# Memory-QSPI_Flash-eMMC.net
KiCad netlist of a schematic drawn in Altium Designer
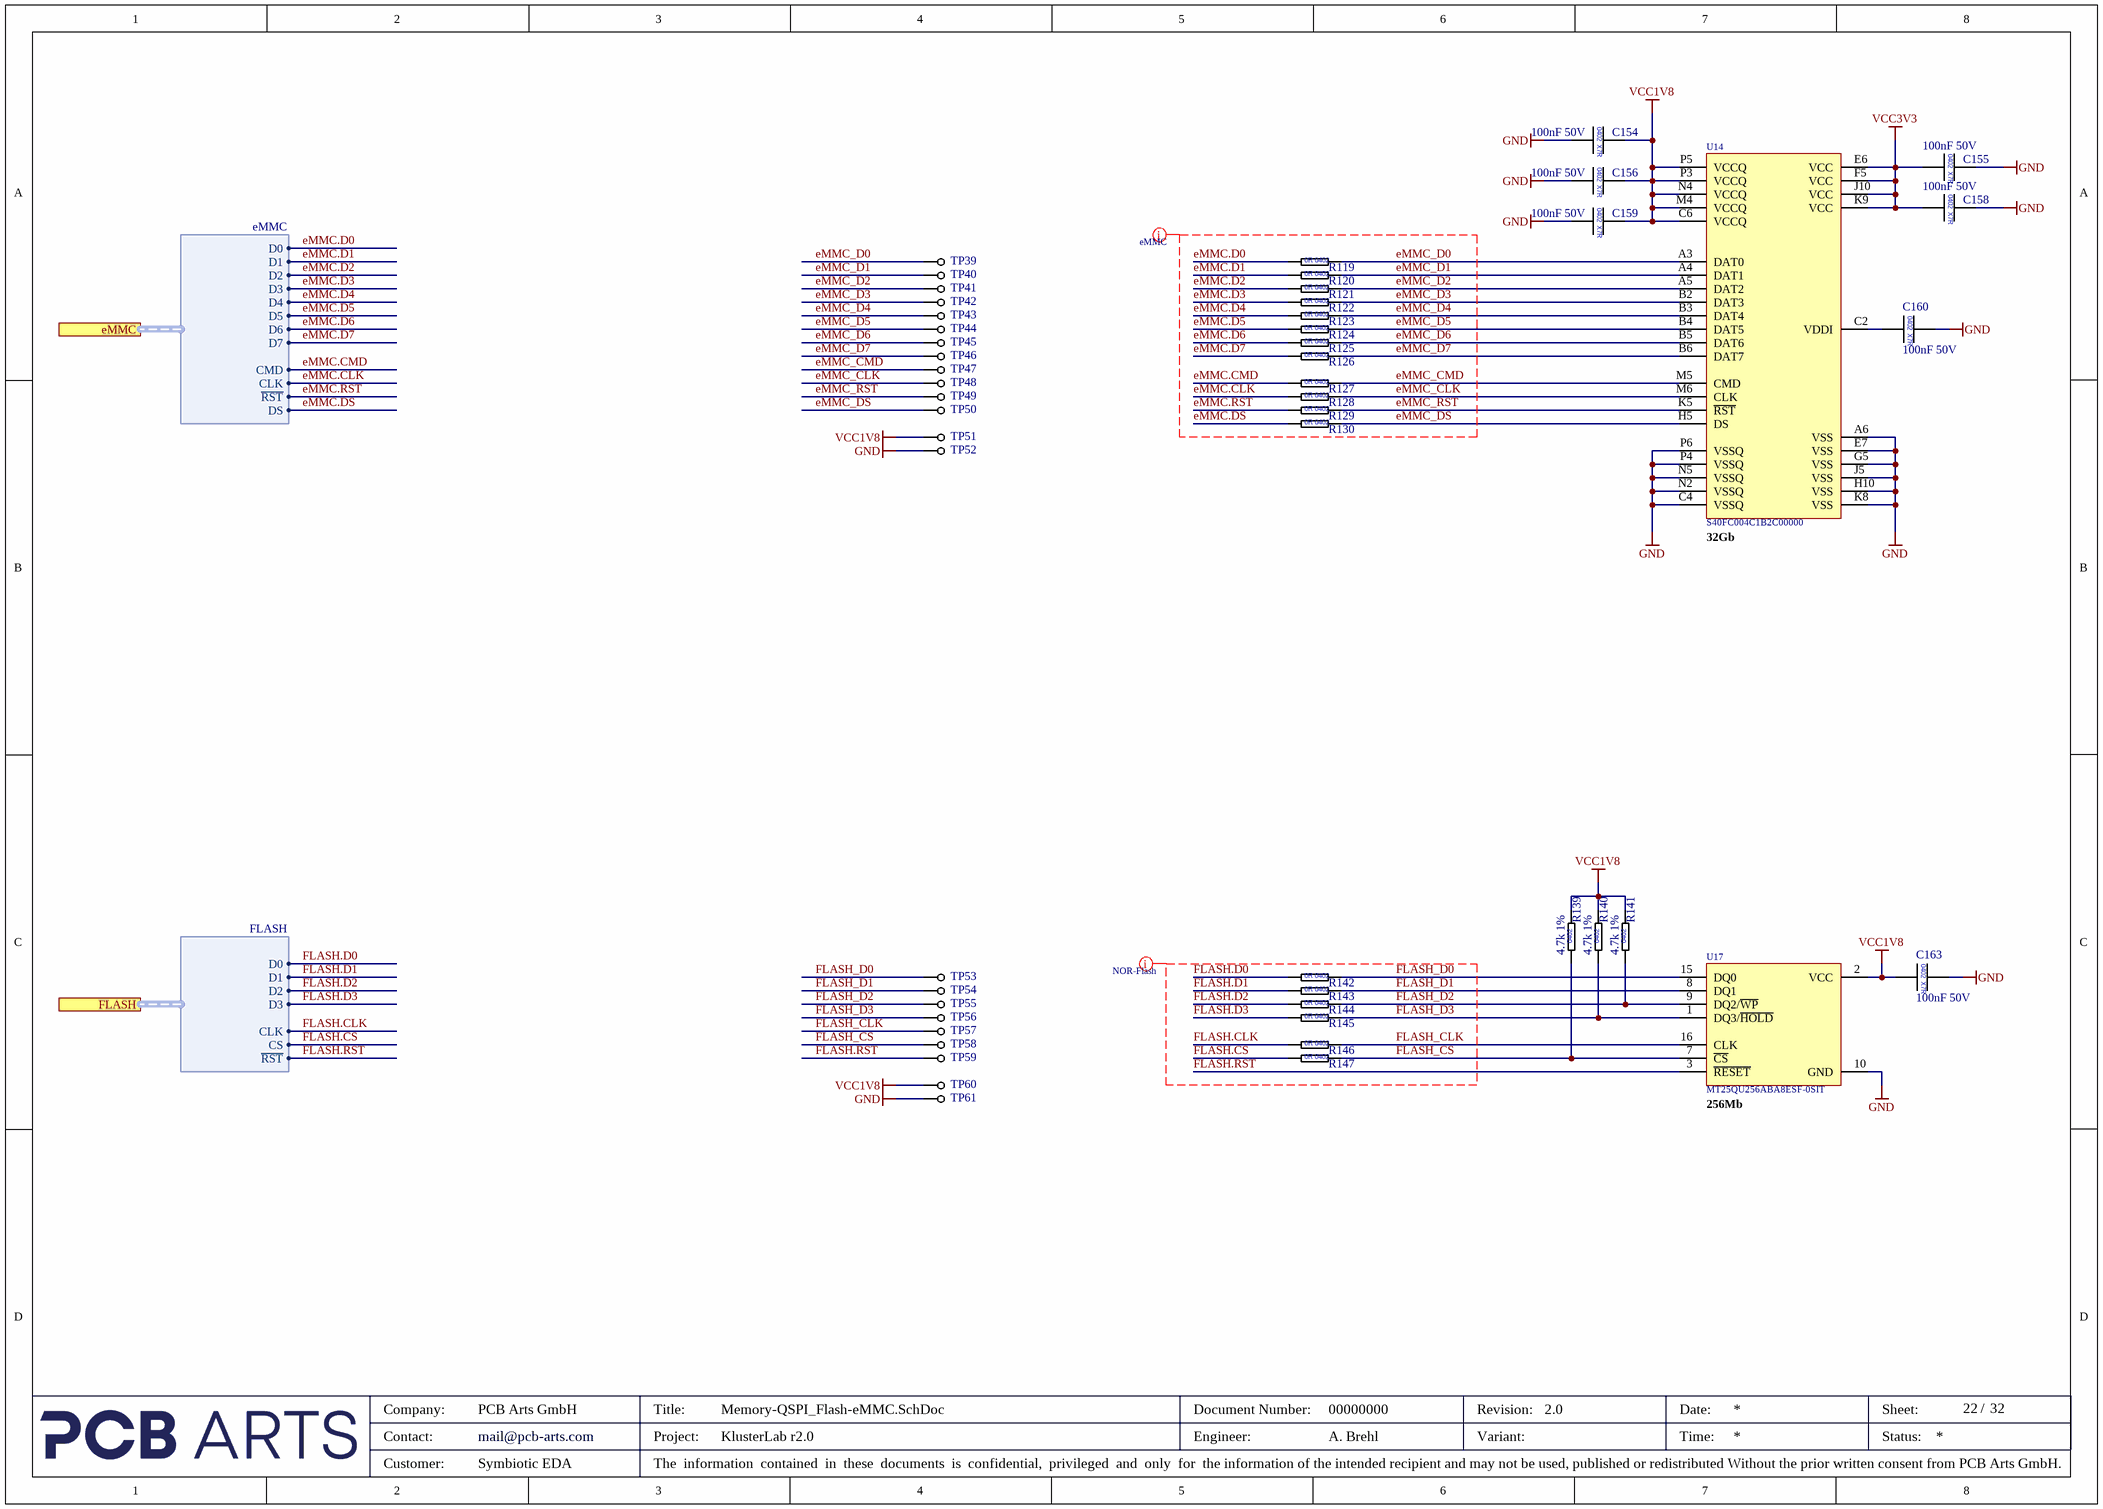
[diagram p0: Memory-QSPI_Flash-eMMC.SchDoc]

(export (version "E")
  (design (tool "Eeschema 10.0.6"))
  (components
    (comp (ref "C154")
      (value "100nF 50V")
      (footprint "Cap:CAP_0402_L")
      (description "Multilayer Ceramic Capacitors MLCC - SMD/SMT 0402 50VDC")
      (libsource (lib "Cap") (part "CAP_0402_100nF_50V"))
    )
    (comp (ref "C155")
      (value "100nF 50V")
      (footprint "Cap:CAP_0402_L")
      (description "Multilayer Ceramic Capacitors MLCC - SMD/SMT 0402 50VDC")
      (libsource (lib "Cap") (part "CAP_0402_100nF_50V"))
    )
    (comp (ref "C156")
      (value "100nF 50V")
      (footprint "Cap:CAP_0402_L")
      (description "Multilayer Ceramic Capacitors MLCC - SMD/SMT 0402 50VDC")
      (libsource (lib "Cap") (part "CAP_0402_100nF_50V"))
    )
    (comp (ref "C158")
      (value "100nF 50V")
      (footprint "Cap:CAP_0402_L")
      (description "Multilayer Ceramic Capacitors MLCC - SMD/SMT 0402 50VDC")
      (libsource (lib "Cap") (part "CAP_0402_100nF_50V"))
    )
    (comp (ref "C159")
      (value "100nF 50V")
      (footprint "Cap:CAP_0402_L")
      (description "Multilayer Ceramic Capacitors MLCC - SMD/SMT 0402 50VDC")
      (libsource (lib "Cap") (part "CAP_0402_100nF_50V"))
    )
    (comp (ref "C160")
      (value "100nF 50V")
      (footprint "Cap:CAP_0402_L")
      (description "Multilayer Ceramic Capacitors MLCC - SMD/SMT 0402 50VDC")
      (libsource (lib "Cap") (part "CAP_0402_100nF_50V"))
    )
    (comp (ref "C163")
      (value "100nF 50V")
      (footprint "Cap:CAP_0402_L")
      (description "Multilayer Ceramic Capacitors MLCC - SMD/SMT 0402 50VDC")
      (libsource (lib "Cap") (part "CAP_0402_100nF_50V"))
    )
    (comp (ref "R119")
      (value "0R Jumper")
      (footprint "Res:RES_0402_L")
      (description "Thick Film Resistors - SMD 0Ohm")
      (libsource (lib "Res") (part "RES_0402_0R Jumper"))
    )
    (comp (ref "R120")
      (value "0R Jumper")
      (footprint "Res:RES_0402_L")
      (description "Thick Film Resistors - SMD 0Ohm")
      (libsource (lib "Res") (part "RES_0402_0R Jumper"))
    )
    (comp (ref "R121")
      (value "0R Jumper")
      (footprint "Res:RES_0402_L")
      (description "Thick Film Resistors - SMD 0Ohm")
      (libsource (lib "Res") (part "RES_0402_0R Jumper"))
    )
    (comp (ref "R122")
      (value "0R Jumper")
      (footprint "Res:RES_0402_L")
      (description "Thick Film Resistors - SMD 0Ohm")
      (libsource (lib "Res") (part "RES_0402_0R Jumper"))
    )
    (comp (ref "R123")
      (value "0R Jumper")
      (footprint "Res:RES_0402_L")
      (description "Thick Film Resistors - SMD 0Ohm")
      (libsource (lib "Res") (part "RES_0402_0R Jumper"))
    )
    (comp (ref "R124")
      (value "0R Jumper")
      (footprint "Res:RES_0402_L")
      (description "Thick Film Resistors - SMD 0Ohm")
      (libsource (lib "Res") (part "RES_0402_0R Jumper"))
    )
    (comp (ref "R125")
      (value "0R Jumper")
      (footprint "Res:RES_0402_L")
      (description "Thick Film Resistors - SMD 0Ohm")
      (libsource (lib "Res") (part "RES_0402_0R Jumper"))
    )
    (comp (ref "R126")
      (value "0R Jumper")
      (footprint "Res:RES_0402_L")
      (description "Thick Film Resistors - SMD 0Ohm")
      (libsource (lib "Res") (part "RES_0402_0R Jumper"))
    )
    (comp (ref "R127")
      (value "0R Jumper")
      (footprint "Res:RES_0402_L")
      (description "Thick Film Resistors - SMD 0Ohm")
      (libsource (lib "Res") (part "RES_0402_0R Jumper"))
    )
    (comp (ref "R128")
      (value "0R Jumper")
      (footprint "Res:RES_0402_L")
      (description "Thick Film Resistors - SMD 0Ohm")
      (libsource (lib "Res") (part "RES_0402_0R Jumper"))
    )
    (comp (ref "R129")
      (value "0R Jumper")
      (footprint "Res:RES_0402_L")
      (description "Thick Film Resistors - SMD 0Ohm")
      (libsource (lib "Res") (part "RES_0402_0R Jumper"))
    )
    (comp (ref "R130")
      (value "0R Jumper")
      (footprint "Res:RES_0402_L")
      (description "Thick Film Resistors - SMD 0Ohm")
      (libsource (lib "Res") (part "RES_0402_0R Jumper"))
    )
    (comp (ref "R139")
      (value "4.7k 1%")
      (footprint "Res:RES_0402_L")
      (description "Thick Film Resistors - SMD 4.7kOhm 1%")
      (libsource (lib "Res") (part "RES_0402_4.7k_1%"))
    )
    (comp (ref "R140")
      (value "4.7k 1%")
      (footprint "Res:RES_0402_L")
      (description "Thick Film Resistors - SMD 4.7kOhm 1%")
      (libsource (lib "Res") (part "RES_0402_4.7k_1%"))
    )
    (comp (ref "R141")
      (value "4.7k 1%")
      (footprint "Res:RES_0402_L")
      (description "Thick Film Resistors - SMD 4.7kOhm 1%")
      (libsource (lib "Res") (part "RES_0402_4.7k_1%"))
    )
    (comp (ref "R142")
      (value "0R Jumper")
      (footprint "Res:RES_0402_L")
      (description "Thick Film Resistors - SMD 0Ohm")
      (libsource (lib "Res") (part "RES_0402_0R Jumper"))
    )
    (comp (ref "R143")
      (value "0R Jumper")
      (footprint "Res:RES_0402_L")
      (description "Thick Film Resistors - SMD 0Ohm")
      (libsource (lib "Res") (part "RES_0402_0R Jumper"))
    )
    (comp (ref "R144")
      (value "0R Jumper")
      (footprint "Res:RES_0402_L")
      (description "Thick Film Resistors - SMD 0Ohm")
      (libsource (lib "Res") (part "RES_0402_0R Jumper"))
    )
    (comp (ref "R145")
      (value "0R Jumper")
      (footprint "Res:RES_0402_L")
      (description "Thick Film Resistors - SMD 0Ohm")
      (libsource (lib "Res") (part "RES_0402_0R Jumper"))
    )
    (comp (ref "R146")
      (value "0R Jumper")
      (footprint "Res:RES_0402_L")
      (description "Thick Film Resistors - SMD 0Ohm")
      (libsource (lib "Res") (part "RES_0402_0R Jumper"))
    )
    (comp (ref "R147")
      (value "0R Jumper")
      (footprint "Res:RES_0402_L")
      (description "Thick Film Resistors - SMD 0Ohm")
      (libsource (lib "Res") (part "RES_0402_0R Jumper"))
    )
    (comp (ref "TP39")
      (value "Testpoint")
      (footprint "Electro_mech:Testpoint 0.8mm")
      (description "Testpoint 0.8mm")
      (libsource (lib "Electro_Mech") (part "Testpoint 0.8mm"))
    )
    (comp (ref "TP40")
      (value "Testpoint")
      (footprint "Electro_mech:Testpoint 0.8mm")
      (description "Testpoint 0.8mm")
      (libsource (lib "Electro_Mech") (part "Testpoint 0.8mm"))
    )
    (comp (ref "TP41")
      (value "Testpoint")
      (footprint "Electro_mech:Testpoint 0.8mm")
      (description "Testpoint 0.8mm")
      (libsource (lib "Electro_Mech") (part "Testpoint 0.8mm"))
    )
    (comp (ref "TP42")
      (value "Testpoint")
      (footprint "Electro_mech:Testpoint 0.8mm")
      (description "Testpoint 0.8mm")
      (libsource (lib "Electro_Mech") (part "Testpoint 0.8mm"))
    )
    (comp (ref "TP43")
      (value "Testpoint")
      (footprint "Electro_mech:Testpoint 0.8mm")
      (description "Testpoint 0.8mm")
      (libsource (lib "Electro_Mech") (part "Testpoint 0.8mm"))
    )
    (comp (ref "TP44")
      (value "Testpoint")
      (footprint "Electro_mech:Testpoint 0.8mm")
      (description "Testpoint 0.8mm")
      (libsource (lib "Electro_Mech") (part "Testpoint 0.8mm"))
    )
    (comp (ref "TP45")
      (value "Testpoint")
      (footprint "Electro_mech:Testpoint 0.8mm")
      (description "Testpoint 0.8mm")
      (libsource (lib "Electro_Mech") (part "Testpoint 0.8mm"))
    )
    (comp (ref "TP46")
      (value "Testpoint")
      (footprint "Electro_mech:Testpoint 0.8mm")
      (description "Testpoint 0.8mm")
      (libsource (lib "Electro_Mech") (part "Testpoint 0.8mm"))
    )
    (comp (ref "TP47")
      (value "Testpoint")
      (footprint "Electro_mech:Testpoint 0.8mm")
      (description "Testpoint 0.8mm")
      (libsource (lib "Electro_Mech") (part "Testpoint 0.8mm"))
    )
    (comp (ref "TP48")
      (value "Testpoint")
      (footprint "Electro_mech:Testpoint 0.8mm")
      (description "Testpoint 0.8mm")
      (libsource (lib "Electro_Mech") (part "Testpoint 0.8mm"))
    )
    (comp (ref "TP49")
      (value "Testpoint")
      (footprint "Electro_mech:Testpoint 0.8mm")
      (description "Testpoint 0.8mm")
      (libsource (lib "Electro_Mech") (part "Testpoint 0.8mm"))
    )
    (comp (ref "TP50")
      (value "Testpoint")
      (footprint "Electro_mech:Testpoint 0.8mm")
      (description "Testpoint 0.8mm")
      (libsource (lib "Electro_Mech") (part "Testpoint 0.8mm"))
    )
    (comp (ref "TP51")
      (value "Testpoint")
      (footprint "Electro_mech:Testpoint 0.8mm")
      (description "Testpoint 0.8mm")
      (libsource (lib "Electro_Mech") (part "Testpoint 0.8mm"))
    )
    (comp (ref "TP52")
      (value "Testpoint")
      (footprint "Electro_mech:Testpoint 0.8mm")
      (description "Testpoint 0.8mm")
      (libsource (lib "Electro_Mech") (part "Testpoint 0.8mm"))
    )
    (comp (ref "TP53")
      (value "Testpoint")
      (footprint "Electro_mech:Testpoint 0.8mm")
      (description "Testpoint 0.8mm")
      (libsource (lib "Electro_Mech") (part "Testpoint 0.8mm"))
    )
    (comp (ref "TP54")
      (value "Testpoint")
      (footprint "Electro_mech:Testpoint 0.8mm")
      (description "Testpoint 0.8mm")
      (libsource (lib "Electro_Mech") (part "Testpoint 0.8mm"))
    )
    (comp (ref "TP55")
      (value "Testpoint")
      (footprint "Electro_mech:Testpoint 0.8mm")
      (description "Testpoint 0.8mm")
      (libsource (lib "Electro_Mech") (part "Testpoint 0.8mm"))
    )
    (comp (ref "TP56")
      (value "Testpoint")
      (footprint "Electro_mech:Testpoint 0.8mm")
      (description "Testpoint 0.8mm")
      (libsource (lib "Electro_Mech") (part "Testpoint 0.8mm"))
    )
    (comp (ref "TP57")
      (value "Testpoint")
      (footprint "Electro_mech:Testpoint 0.8mm")
      (description "Testpoint 0.8mm")
      (libsource (lib "Electro_Mech") (part "Testpoint 0.8mm"))
    )
    (comp (ref "TP58")
      (value "Testpoint")
      (footprint "Electro_mech:Testpoint 0.8mm")
      (description "Testpoint 0.8mm")
      (libsource (lib "Electro_Mech") (part "Testpoint 0.8mm"))
    )
    (comp (ref "TP59")
      (value "Testpoint")
      (footprint "Electro_mech:Testpoint 0.8mm")
      (description "Testpoint 0.8mm")
      (libsource (lib "Electro_Mech") (part "Testpoint 0.8mm"))
    )
    (comp (ref "TP60")
      (value "Testpoint")
      (footprint "Electro_mech:Testpoint 0.8mm")
      (description "Testpoint 0.8mm")
      (libsource (lib "Electro_Mech") (part "Testpoint 0.8mm"))
    )
    (comp (ref "TP61")
      (value "Testpoint")
      (footprint "Electro_mech:Testpoint 0.8mm")
      (description "Testpoint 0.8mm")
      (libsource (lib "Electro_Mech") (part "Testpoint 0.8mm"))
    )
    (comp (ref "U14")
      (value "S40FC004C1B2C00000")
      (footprint "Digital:BGA50P900X750X080-153N")
      (description "eMMC 4GB e.MMC5.1 BGA 9.0 x 7.5 x 0.8 mm")
      (libsource (lib "Digital") (part "S40FC004C1B2C00000_eMMC 4GB e.MMC5.1 BGA 9.0 x 7.5 x 0.8 mm"))
    )
    (comp (ref "U17")
      (value "MT25QU256ABA8ESF-0SIT")
      (footprint "Digital:SOIC16_Widebody")
      (description "NOR-Flash SPI 256Mbit NOR-Flash /1.8V")
      (libsource (lib "Digital") (part "MT25QU256ABA8ESF-0SIT_NOR-Flash SPI 256Mbit NOR-Flash /1.8V"))
    )
  )
  (nets
    (net (code "3") (name "/FLASH.CLK") (class "Default")
      (node (ref "R146") (pin "1") (pinfunction "1_1") (pintype "passive"))
    )
    (net (code "4") (name "/FLASH.D0") (class "Default")
      (node (ref "R142") (pin "1") (pinfunction "1_1") (pintype "passive"))
    )
    (net (code "5") (name "/FLASH.D1") (class "Default")
      (node (ref "R143") (pin "1") (pinfunction "1_1") (pintype "passive"))
    )
    (net (code "6") (name "/FLASH.D2") (class "Default")
      (node (ref "R144") (pin "1") (pinfunction "1_1") (pintype "passive"))
    )
    (net (code "7") (name "/FLASH.D3") (class "Default")
      (node (ref "R145") (pin "1") (pinfunction "1_1") (pintype "passive"))
    )
    (net (code "8") (name "/FLASH.~{CS}") (class "Default")
      (node (ref "R147") (pin "1") (pinfunction "1_1") (pintype "passive"))
    )
    (net (code "9") (name "/FLASH.~{RST}") (class "Default")
      (node (ref "TP59") (pin "1") (pinfunction "GND_1") (pintype "passive"))
      (node (ref "U17") (pin "3") (pinfunction "~{RESET}_3") (pintype "passive"))
    )
    (net (code "10") (name "/FLASH_CLK") (class "Default")
      (node (ref "R146") (pin "2") (pinfunction "2_2") (pintype "passive"))
      (node (ref "TP57") (pin "1") (pinfunction "GND_1") (pintype "passive"))
      (node (ref "U17") (pin "16") (pinfunction "CLK_16") (pintype "passive"))
    )
    (net (code "11") (name "/FLASH_D0") (class "Default")
      (node (ref "R142") (pin "2") (pinfunction "2_2") (pintype "passive"))
      (node (ref "TP53") (pin "1") (pinfunction "GND_1") (pintype "passive"))
      (node (ref "U17") (pin "15") (pinfunction "DQ0_15") (pintype "passive"))
    )
    (net (code "12") (name "/FLASH_D1") (class "Default")
      (node (ref "R143") (pin "2") (pinfunction "2_2") (pintype "passive"))
      (node (ref "TP54") (pin "1") (pinfunction "GND_1") (pintype "passive"))
      (node (ref "U17") (pin "8") (pinfunction "DQ1_8") (pintype "passive"))
    )
    (net (code "13") (name "/FLASH_D2") (class "Default")
      (node (ref "R141") (pin "1") (pinfunction "1_1") (pintype "passive"))
      (node (ref "R144") (pin "2") (pinfunction "2_2") (pintype "passive"))
      (node (ref "TP55") (pin "1") (pinfunction "GND_1") (pintype "passive"))
      (node (ref "U17") (pin "9") (pinfunction "DQ2/~{WP}_9") (pintype "passive"))
    )
    (net (code "14") (name "/FLASH_D3") (class "Default")
      (node (ref "R140") (pin "1") (pinfunction "1_1") (pintype "passive"))
      (node (ref "R145") (pin "2") (pinfunction "2_2") (pintype "passive"))
      (node (ref "TP56") (pin "1") (pinfunction "GND_1") (pintype "passive"))
      (node (ref "U17") (pin "1") (pinfunction "DQ3/~{HOLD}_1") (pintype "passive"))
    )
    (net (code "15") (name "/FLASH_~{CS}") (class "Default")
      (node (ref "R139") (pin "1") (pinfunction "1_1") (pintype "passive"))
      (node (ref "R147") (pin "2") (pinfunction "2_2") (pintype "passive"))
      (node (ref "TP58") (pin "1") (pinfunction "GND_1") (pintype "passive"))
      (node (ref "U17") (pin "7") (pinfunction "~{CS}_7") (pintype "passive"))
    )
    (net (code "16") (name "/eMMC.CLK") (class "Default")
      (node (ref "R128") (pin "1") (pinfunction "1_1") (pintype "passive"))
    )
    (net (code "17") (name "/eMMC.CMD") (class "Default")
      (node (ref "R127") (pin "1") (pinfunction "1_1") (pintype "passive"))
    )
    (net (code "18") (name "/eMMC.D0") (class "Default")
      (node (ref "R119") (pin "1") (pinfunction "1_1") (pintype "passive"))
    )
    (net (code "19") (name "/eMMC.D1") (class "Default")
      (node (ref "R120") (pin "1") (pinfunction "1_1") (pintype "passive"))
    )
    (net (code "20") (name "/eMMC.D2") (class "Default")
      (node (ref "R121") (pin "1") (pinfunction "1_1") (pintype "passive"))
    )
    (net (code "21") (name "/eMMC.D3") (class "Default")
      (node (ref "R122") (pin "1") (pinfunction "1_1") (pintype "passive"))
    )
    (net (code "22") (name "/eMMC.D4") (class "Default")
      (node (ref "R123") (pin "1") (pinfunction "1_1") (pintype "passive"))
    )
    (net (code "23") (name "/eMMC.D5") (class "Default")
      (node (ref "R124") (pin "1") (pinfunction "1_1") (pintype "passive"))
    )
    (net (code "24") (name "/eMMC.D6") (class "Default")
      (node (ref "R125") (pin "1") (pinfunction "1_1") (pintype "passive"))
    )
    (net (code "25") (name "/eMMC.D7") (class "Default")
      (node (ref "R126") (pin "1") (pinfunction "1_1") (pintype "passive"))
    )
    (net (code "26") (name "/eMMC.DS") (class "Default")
      (node (ref "R130") (pin "1") (pinfunction "1_1") (pintype "passive"))
    )
    (net (code "27") (name "/eMMC.~{RST}") (class "Default")
      (node (ref "R129") (pin "1") (pinfunction "1_1") (pintype "passive"))
    )
    (net (code "28") (name "/eMMC_CLK") (class "Default")
      (node (ref "R128") (pin "2") (pinfunction "2_2") (pintype "passive"))
      (node (ref "TP48") (pin "1") (pinfunction "GND_1") (pintype "passive"))
      (node (ref "U14") (pin "M6") (pinfunction "CLK_M6") (pintype "passive"))
    )
    (net (code "29") (name "/eMMC_CMD") (class "Default")
      (node (ref "R127") (pin "2") (pinfunction "2_2") (pintype "passive"))
      (node (ref "TP47") (pin "1") (pinfunction "GND_1") (pintype "passive"))
      (node (ref "U14") (pin "M5") (pinfunction "CMD_M5") (pintype "passive"))
    )
    (net (code "30") (name "/eMMC_D0") (class "Default")
      (node (ref "R119") (pin "2") (pinfunction "2_2") (pintype "passive"))
      (node (ref "TP39") (pin "1") (pinfunction "GND_1") (pintype "passive"))
      (node (ref "U14") (pin "A3") (pinfunction "DAT0_A3") (pintype "passive"))
    )
    (net (code "31") (name "/eMMC_D1") (class "Default")
      (node (ref "R120") (pin "2") (pinfunction "2_2") (pintype "passive"))
      (node (ref "TP40") (pin "1") (pinfunction "GND_1") (pintype "passive"))
      (node (ref "U14") (pin "A4") (pinfunction "DAT1_A4") (pintype "passive"))
    )
    (net (code "32") (name "/eMMC_D2") (class "Default")
      (node (ref "R121") (pin "2") (pinfunction "2_2") (pintype "passive"))
      (node (ref "TP41") (pin "1") (pinfunction "GND_1") (pintype "passive"))
      (node (ref "U14") (pin "A5") (pinfunction "DAT2_A5") (pintype "passive"))
    )
    (net (code "33") (name "/eMMC_D3") (class "Default")
      (node (ref "R122") (pin "2") (pinfunction "2_2") (pintype "passive"))
      (node (ref "TP42") (pin "1") (pinfunction "GND_1") (pintype "passive"))
      (node (ref "U14") (pin "B2") (pinfunction "DAT3_B2") (pintype "passive"))
    )
    (net (code "34") (name "/eMMC_D4") (class "Default")
      (node (ref "R123") (pin "2") (pinfunction "2_2") (pintype "passive"))
      (node (ref "TP43") (pin "1") (pinfunction "GND_1") (pintype "passive"))
      (node (ref "U14") (pin "B3") (pinfunction "DAT4_B3") (pintype "passive"))
    )
    (net (code "35") (name "/eMMC_D5") (class "Default")
      (node (ref "R124") (pin "2") (pinfunction "2_2") (pintype "passive"))
      (node (ref "TP44") (pin "1") (pinfunction "GND_1") (pintype "passive"))
      (node (ref "U14") (pin "B4") (pinfunction "DAT5_B4") (pintype "passive"))
    )
    (net (code "36") (name "/eMMC_D6") (class "Default")
      (node (ref "R125") (pin "2") (pinfunction "2_2") (pintype "passive"))
      (node (ref "TP45") (pin "1") (pinfunction "GND_1") (pintype "passive"))
      (node (ref "U14") (pin "B5") (pinfunction "DAT6_B5") (pintype "passive"))
    )
    (net (code "37") (name "/eMMC_D7") (class "Default")
      (node (ref "R126") (pin "2") (pinfunction "2_2") (pintype "passive"))
      (node (ref "TP46") (pin "1") (pinfunction "GND_1") (pintype "passive"))
      (node (ref "U14") (pin "B6") (pinfunction "DAT7_B6") (pintype "passive"))
    )
    (net (code "38") (name "/eMMC_DS") (class "Default")
      (node (ref "R130") (pin "2") (pinfunction "2_2") (pintype "passive"))
      (node (ref "TP50") (pin "1") (pinfunction "GND_1") (pintype "passive"))
      (node (ref "U14") (pin "H5") (pinfunction "DS_H5") (pintype "passive"))
    )
    (net (code "39") (name "/eMMC_~{RST}") (class "Default")
      (node (ref "R129") (pin "2") (pinfunction "2_2") (pintype "passive"))
      (node (ref "TP49") (pin "1") (pinfunction "GND_1") (pintype "passive"))
      (node (ref "U14") (pin "K5") (pinfunction "~{RST}_K5") (pintype "passive"))
    )
    (net (code "42") (name "GND") (class "Default")
      (node (ref "C154") (pin "2") (pinfunction "2_2") (pintype "passive"))
      (node (ref "C155") (pin "1") (pinfunction "1_1") (pintype "passive"))
      (node (ref "C156") (pin "2") (pinfunction "2_2") (pintype "passive"))
      (node (ref "C158") (pin "1") (pinfunction "1_1") (pintype "passive"))
      (node (ref "C159") (pin "2") (pinfunction "2_2") (pintype "passive"))
      (node (ref "C160") (pin "1") (pinfunction "1_1") (pintype "passive"))
      (node (ref "C163") (pin "1") (pinfunction "1_1") (pintype "passive"))
      (node (ref "TP52") (pin "1") (pinfunction "GND_1") (pintype "passive"))
      (node (ref "TP61") (pin "1") (pinfunction "GND_1") (pintype "passive"))
      (node (ref "U14") (pin "A6") (pinfunction "VSS_A6") (pintype "passive"))
      (node (ref "U14") (pin "C4") (pinfunction "VSSQ_C4") (pintype "passive"))
      (node (ref "U14") (pin "E7") (pinfunction "VSS_E7") (pintype "passive"))
      (node (ref "U14") (pin "G5") (pinfunction "VSS_G5") (pintype "passive"))
      (node (ref "U14") (pin "H10") (pinfunction "VSS_H10") (pintype "passive"))
      (node (ref "U14") (pin "J5") (pinfunction "VSS_J5") (pintype "passive"))
      (node (ref "U14") (pin "K8") (pinfunction "VSS_K8") (pintype "passive"))
      (node (ref "U14") (pin "N2") (pinfunction "VSSQ_N2") (pintype "passive"))
      (node (ref "U14") (pin "N5") (pinfunction "VSSQ_N5") (pintype "passive"))
      (node (ref "U14") (pin "P4") (pinfunction "VSSQ_P4") (pintype "passive"))
      (node (ref "U14") (pin "P6") (pinfunction "VSSQ_P6") (pintype "passive"))
      (node (ref "U17") (pin "10") (pinfunction "GND_10") (pintype "passive"))
    )
    (net (code "43") (name "Net-(U14-VDDI)") (class "Default")
      (node (ref "C160") (pin "2") (pinfunction "2_2") (pintype "passive"))
      (node (ref "U14") (pin "C2") (pinfunction "VDDI_C2") (pintype "passive"))
    )
    (net (code "44") (name "VCC1V8") (class "Default")
      (node (ref "C154") (pin "1") (pinfunction "1_1") (pintype "passive"))
      (node (ref "C156") (pin "1") (pinfunction "1_1") (pintype "passive"))
      (node (ref "C159") (pin "1") (pinfunction "1_1") (pintype "passive"))
      (node (ref "C163") (pin "2") (pinfunction "2_2") (pintype "passive"))
      (node (ref "R139") (pin "2") (pinfunction "2_2") (pintype "passive"))
      (node (ref "R140") (pin "2") (pinfunction "2_2") (pintype "passive"))
      (node (ref "R141") (pin "2") (pinfunction "2_2") (pintype "passive"))
      (node (ref "TP51") (pin "1") (pinfunction "GND_1") (pintype "passive"))
      (node (ref "TP60") (pin "1") (pinfunction "GND_1") (pintype "passive"))
      (node (ref "U14") (pin "C6") (pinfunction "VCCQ_C6") (pintype "passive"))
      (node (ref "U14") (pin "M4") (pinfunction "VCCQ_M4") (pintype "passive"))
      (node (ref "U14") (pin "N4") (pinfunction "VCCQ_N4") (pintype "passive"))
      (node (ref "U14") (pin "P3") (pinfunction "VCCQ_P3") (pintype "passive"))
      (node (ref "U14") (pin "P5") (pinfunction "VCCQ_P5") (pintype "passive"))
      (node (ref "U17") (pin "2") (pinfunction "VCC_2") (pintype "passive"))
    )
    (net (code "45") (name "VCC3V3") (class "Default")
      (node (ref "C155") (pin "2") (pinfunction "2_2") (pintype "passive"))
      (node (ref "C158") (pin "2") (pinfunction "2_2") (pintype "passive"))
      (node (ref "U14") (pin "E6") (pinfunction "VCC_E6") (pintype "passive"))
      (node (ref "U14") (pin "F5") (pinfunction "VCC_F5") (pintype "passive"))
      (node (ref "U14") (pin "J10") (pinfunction "VCC_J10") (pintype "passive"))
      (node (ref "U14") (pin "K9") (pinfunction "VCC_K9") (pintype "passive"))
    )
  )
)
